# Connectors.net
KiCad netlist of a schematic drawn in Altium Designer
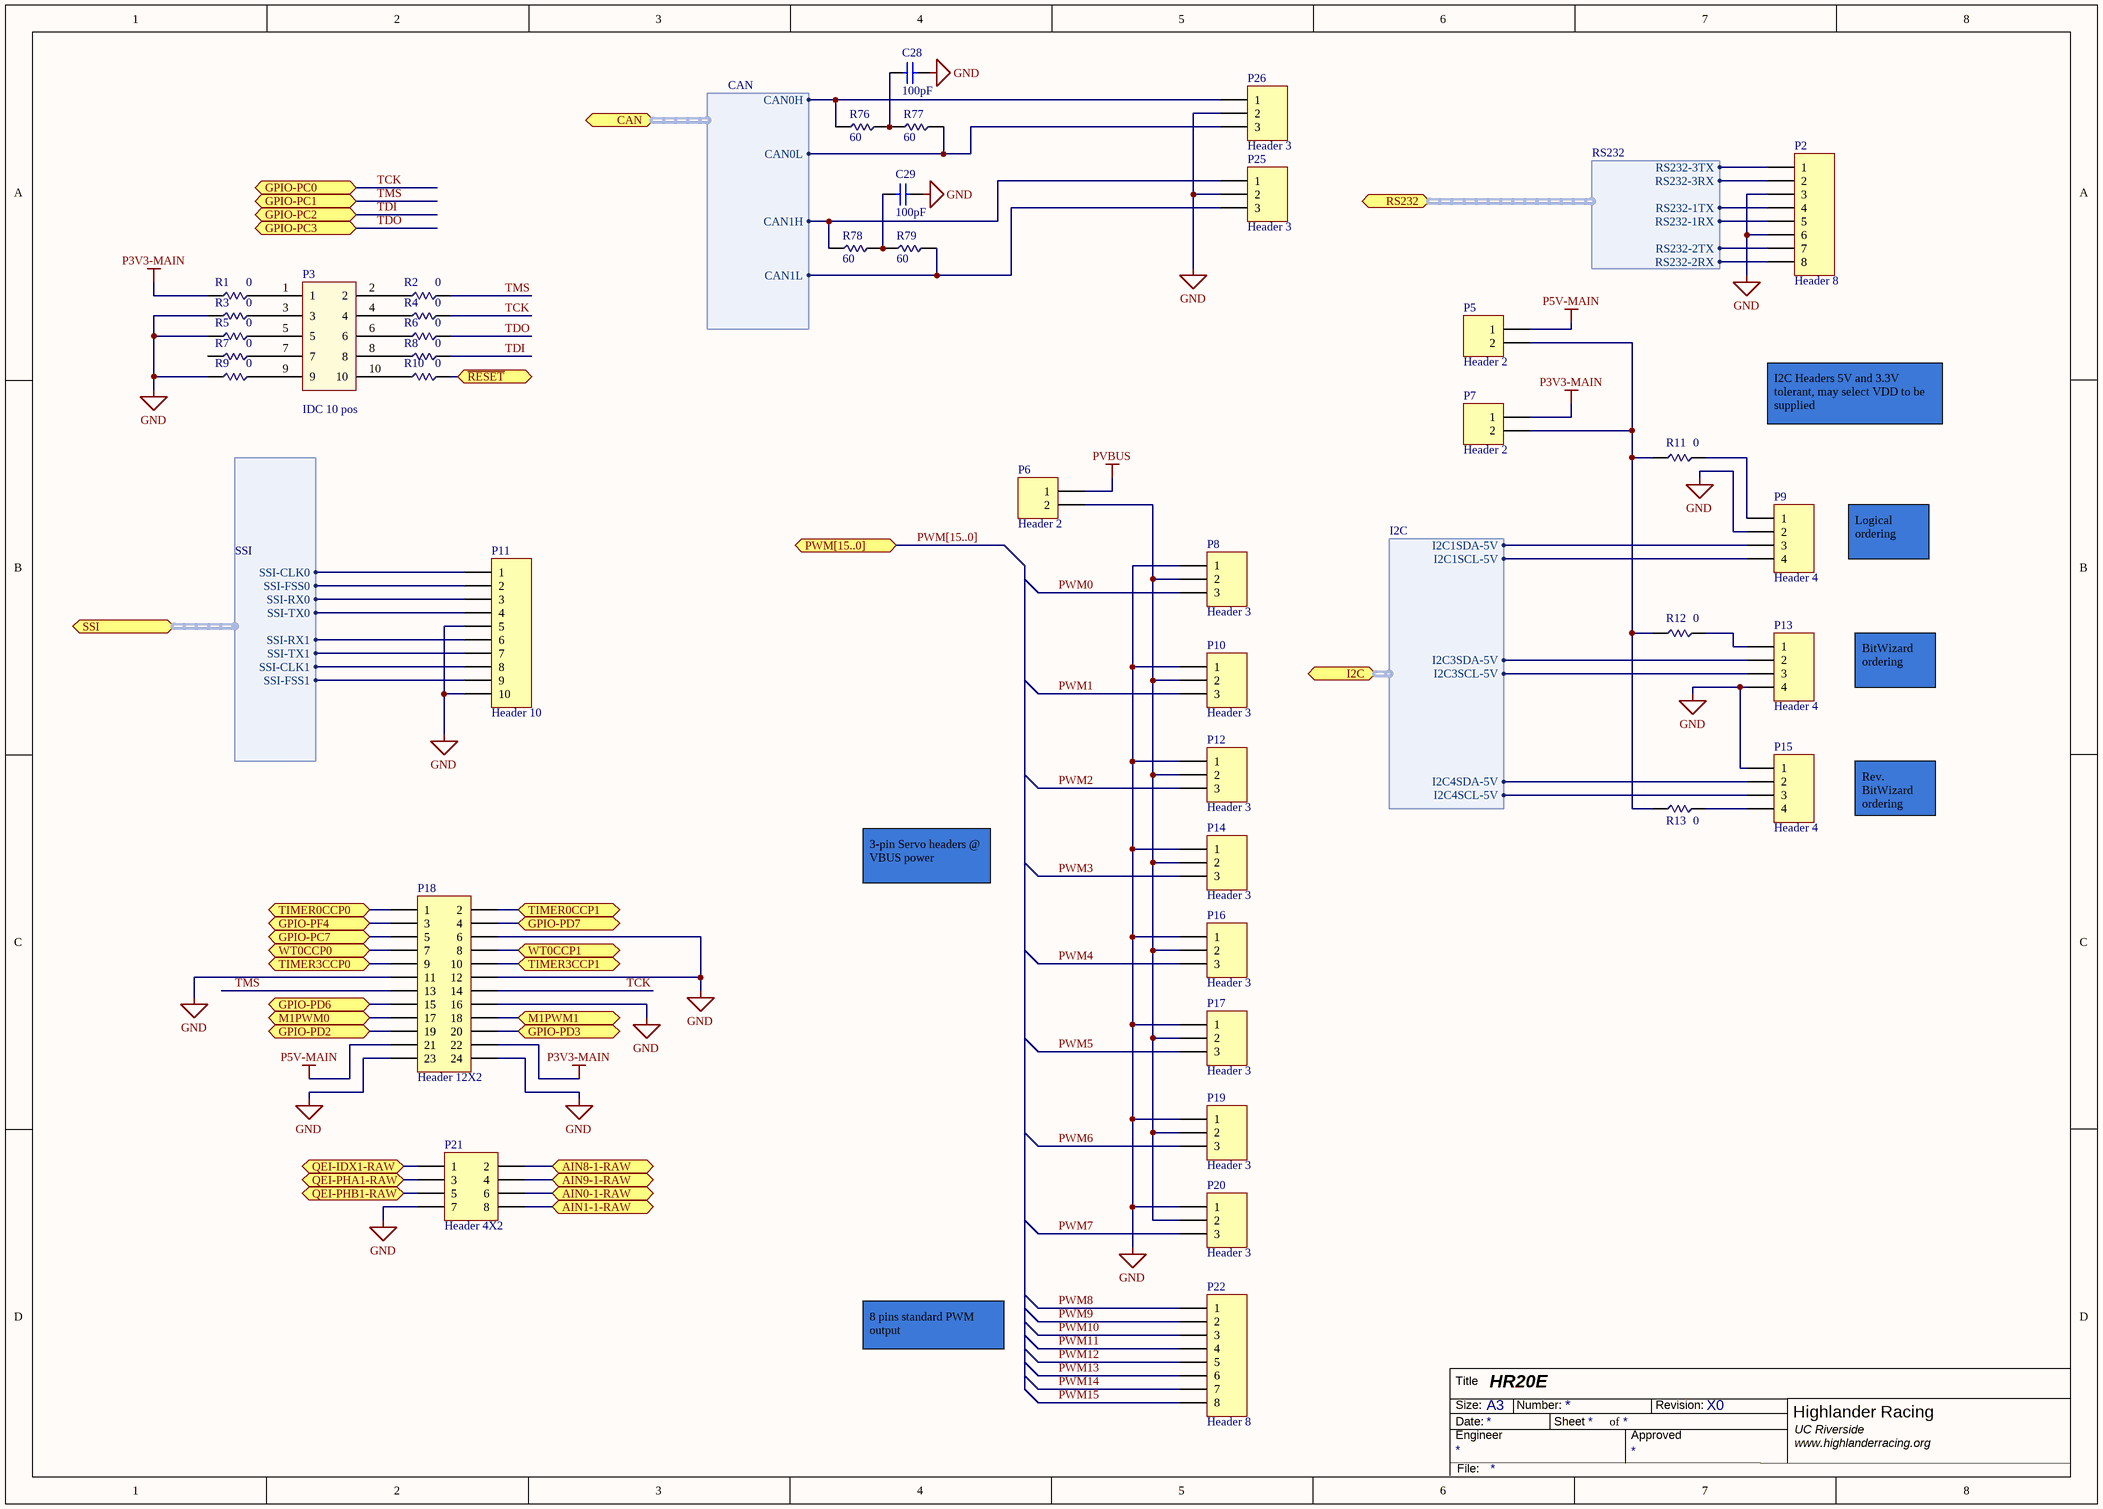
[diagram p0: Connectors.SchDoc]

(export (version "E")
  (design (tool "Eeschema 10.0.6"))
  (components
    (comp (ref "C28")
      (value "100pF")
      (footprint "FOOTPRINT-0805-GEN")
      (description "Capacitor")
      (fields (field (name "Comment") "Capacitor-Generic-0805") (field (name "PUBLISHER") "Altium Limited"))
      (libsource (lib "HR-Master-Integrated") (part "Capacitor-Generic-0805"))
    )
    (comp (ref "C29")
      (value "100pF")
      (footprint "FOOTPRINT-0805-GEN")
      (description "Capacitor")
      (fields (field (name "Comment") "Capacitor-Generic-0805") (field (name "PUBLISHER") "Altium Limited"))
      (libsource (lib "HR-Master-Integrated") (part "Capacitor-Generic-0805"))
    )
    (comp (ref "P2")
      (value "Header 8")
      (footprint "HDR1X8")
      (description "Header, 8-Pin")
      (fields (field (name "PUBLISHER") "Altium Limited"))
      (libsource (lib "AT-Misc-Connectors") (part "Header 8"))
    )
    (comp (ref "P3")
      (value "IDC 10 pos")
      (footprint "FOOTPRINT-GENERIC-10-HEADER-0MM5")
      (libsource (lib "HR-Master-Integrated") (part "Connector-Generic-Header-10-0mm5"))
    )
    (comp (ref "P5")
      (value "Header 2")
      (footprint "HDR1X2")
      (description "Header, 2-Pin")
      (fields (field (name "PUBLISHER") "Altium Limited"))
      (libsource (lib "AT-Misc-Connectors") (part "Header 2"))
    )
    (comp (ref "P6")
      (value "Header 2")
      (footprint "HDR1X2")
      (description "Header, 2-Pin")
      (fields (field (name "PUBLISHER") "Altium Limited"))
      (libsource (lib "AT-Misc-Connectors") (part "Header 2"))
    )
    (comp (ref "P7")
      (value "Header 2")
      (footprint "HDR1X2")
      (description "Header, 2-Pin")
      (fields (field (name "PUBLISHER") "Altium Limited"))
      (libsource (lib "AT-Misc-Connectors") (part "Header 2"))
    )
    (comp (ref "P8")
      (value "Header 3")
      (footprint "HDR1X3")
      (description "Header, 3-Pin")
      (fields (field (name "PUBLISHER") "Altium Limited"))
      (libsource (lib "AT-Misc-Connectors") (part "Header 3"))
    )
    (comp (ref "P9")
      (value "Header 4")
      (footprint "HDR1X4")
      (description "Header, 4-Pin")
      (fields (field (name "PUBLISHER") "Altium Limited"))
      (libsource (lib "AT-Misc-Connectors") (part "Header 4"))
    )
    (comp (ref "P10")
      (value "Header 3")
      (footprint "HDR1X3")
      (description "Header, 3-Pin")
      (fields (field (name "PUBLISHER") "Altium Limited"))
      (libsource (lib "AT-Misc-Connectors") (part "Header 3"))
    )
    (comp (ref "P11")
      (value "Header 10")
      (footprint "HDR1X10")
      (description "Header, 10-Pin")
      (fields (field (name "PUBLISHER") "Altium Limited"))
      (libsource (lib "AT-Misc-Connectors") (part "Header 10"))
    )
    (comp (ref "P12")
      (value "Header 3")
      (footprint "HDR1X3")
      (description "Header, 3-Pin")
      (fields (field (name "PUBLISHER") "Altium Limited"))
      (libsource (lib "AT-Misc-Connectors") (part "Header 3"))
    )
    (comp (ref "P13")
      (value "Header 4")
      (footprint "HDR1X4")
      (description "Header, 4-Pin")
      (fields (field (name "PUBLISHER") "Altium Limited"))
      (libsource (lib "AT-Misc-Connectors") (part "Header 4"))
    )
    (comp (ref "P14")
      (value "Header 3")
      (footprint "HDR1X3")
      (description "Header, 3-Pin")
      (fields (field (name "PUBLISHER") "Altium Limited"))
      (libsource (lib "AT-Misc-Connectors") (part "Header 3"))
    )
    (comp (ref "P15")
      (value "Header 4")
      (footprint "HDR1X4")
      (description "Header, 4-Pin")
      (fields (field (name "PUBLISHER") "Altium Limited"))
      (libsource (lib "AT-Misc-Connectors") (part "Header 4"))
    )
    (comp (ref "P16")
      (value "Header 3")
      (footprint "HDR1X3")
      (description "Header, 3-Pin")
      (fields (field (name "PUBLISHER") "Altium Limited"))
      (libsource (lib "AT-Misc-Connectors") (part "Header 3"))
    )
    (comp (ref "P17")
      (value "Header 3")
      (footprint "HDR1X3")
      (description "Header, 3-Pin")
      (fields (field (name "PUBLISHER") "Altium Limited"))
      (libsource (lib "AT-Misc-Connectors") (part "Header 3"))
    )
    (comp (ref "P18")
      (value "Header 12X2")
      (footprint "HDR2X12")
      (description "Header, 12-Pin, Dual row")
      (fields (field (name "PUBLISHER") "Altium Limited"))
      (libsource (lib "AT-Misc-Connectors") (part "Header 12X2"))
    )
    (comp (ref "P19")
      (value "Header 3")
      (footprint "HDR1X3")
      (description "Header, 3-Pin")
      (fields (field (name "PUBLISHER") "Altium Limited"))
      (libsource (lib "AT-Misc-Connectors") (part "Header 3"))
    )
    (comp (ref "P20")
      (value "Header 3")
      (footprint "HDR1X3")
      (description "Header, 3-Pin")
      (fields (field (name "PUBLISHER") "Altium Limited"))
      (libsource (lib "AT-Misc-Connectors") (part "Header 3"))
    )
    (comp (ref "P21")
      (value "Header 4X2")
      (footprint "HDR2X4")
      (description "Header, 4-Pin, Dual row")
      (fields (field (name "PUBLISHER") "Altium Limited"))
      (libsource (lib "AT-Misc-Connectors") (part "Header 4X2"))
    )
    (comp (ref "P22")
      (value "Header 8")
      (footprint "HDR1X8")
      (description "Header, 8-Pin")
      (fields (field (name "PUBLISHER") "Altium Limited"))
      (libsource (lib "AT-Misc-Connectors") (part "Header 8"))
    )
    (comp (ref "P25")
      (value "Header 3")
      (footprint "HDR1X3")
      (description "Header, 3-Pin")
      (fields (field (name "PUBLISHER") "Altium Limited"))
      (libsource (lib "AT-Misc-Connectors") (part "Header 3"))
    )
    (comp (ref "P26")
      (value "Header 3")
      (footprint "HDR1X3")
      (description "Header, 3-Pin")
      (fields (field (name "PUBLISHER") "Altium Limited"))
      (libsource (lib "AT-Misc-Connectors") (part "Header 3"))
    )
    (comp (ref "R1")
      (value "0")
      (footprint "FOOTPRINT-0805-GEN")
      (description "1/8 Watt Surface Mount Resistor")
      (fields (field (name "Comment") "SMC"))
      (libsource (lib "HR-Master-Integrated") (part "Resistor-Generic-0805-2012"))
    )
    (comp (ref "R2")
      (value "0")
      (footprint "FOOTPRINT-0805-GEN")
      (description "1/8 Watt Surface Mount Resistor")
      (fields (field (name "Comment") "SMC"))
      (libsource (lib "HR-Master-Integrated") (part "Resistor-Generic-0805-2012"))
    )
    (comp (ref "R3")
      (value "0")
      (footprint "FOOTPRINT-0805-GEN")
      (description "1/8 Watt Surface Mount Resistor")
      (fields (field (name "Comment") "SMC"))
      (libsource (lib "HR-Master-Integrated") (part "Resistor-Generic-0805-2012"))
    )
    (comp (ref "R4")
      (value "0")
      (footprint "FOOTPRINT-0805-GEN")
      (description "1/8 Watt Surface Mount Resistor")
      (fields (field (name "Comment") "SMC"))
      (libsource (lib "HR-Master-Integrated") (part "Resistor-Generic-0805-2012"))
    )
    (comp (ref "R5")
      (value "0")
      (footprint "FOOTPRINT-0805-GEN")
      (description "1/8 Watt Surface Mount Resistor")
      (fields (field (name "Comment") "SMC"))
      (libsource (lib "HR-Master-Integrated") (part "Resistor-Generic-0805-2012"))
    )
    (comp (ref "R6")
      (value "0")
      (footprint "FOOTPRINT-0805-GEN")
      (description "1/8 Watt Surface Mount Resistor")
      (fields (field (name "Comment") "SMC"))
      (libsource (lib "HR-Master-Integrated") (part "Resistor-Generic-0805-2012"))
    )
    (comp (ref "R7")
      (value "0")
      (footprint "FOOTPRINT-0805-GEN")
      (description "1/8 Watt Surface Mount Resistor")
      (fields (field (name "Comment") "SMC"))
      (libsource (lib "HR-Master-Integrated") (part "Resistor-Generic-0805-2012"))
    )
    (comp (ref "R8")
      (value "0")
      (footprint "FOOTPRINT-0805-GEN")
      (description "1/8 Watt Surface Mount Resistor")
      (fields (field (name "Comment") "SMC"))
      (libsource (lib "HR-Master-Integrated") (part "Resistor-Generic-0805-2012"))
    )
    (comp (ref "R9")
      (value "0")
      (footprint "FOOTPRINT-0805-GEN")
      (description "1/8 Watt Surface Mount Resistor")
      (fields (field (name "Comment") "SMC"))
      (libsource (lib "HR-Master-Integrated") (part "Resistor-Generic-0805-2012"))
    )
    (comp (ref "R10")
      (value "0")
      (footprint "FOOTPRINT-0805-GEN")
      (description "1/8 Watt Surface Mount Resistor")
      (fields (field (name "Comment") "SMC"))
      (libsource (lib "HR-Master-Integrated") (part "Resistor-Generic-0805-2012"))
    )
    (comp (ref "R11")
      (value "0")
      (footprint "FOOTPRINT-0805-GEN")
      (description "1/8 Watt Surface Mount Resistor")
      (fields (field (name "Comment") "SMC"))
      (libsource (lib "HR-Master-Integrated") (part "Resistor-Generic-0805-2012"))
    )
    (comp (ref "R12")
      (value "0")
      (footprint "FOOTPRINT-0805-GEN")
      (description "1/8 Watt Surface Mount Resistor")
      (fields (field (name "Comment") "SMC"))
      (libsource (lib "HR-Master-Integrated") (part "Resistor-Generic-0805-2012"))
    )
    (comp (ref "R13")
      (value "0")
      (footprint "FOOTPRINT-0805-GEN")
      (description "1/8 Watt Surface Mount Resistor")
      (fields (field (name "Comment") "SMC"))
      (libsource (lib "HR-Master-Integrated") (part "Resistor-Generic-0805-2012"))
    )
    (comp (ref "R76")
      (value "60")
      (footprint "FOOTPRINT-0805-GEN")
      (description "1/8 Watt Surface Mount Resistor")
      (fields (field (name "Comment") "SMC"))
      (libsource (lib "HR-Master-Integrated") (part "Resistor-Generic-0805-2012"))
    )
    (comp (ref "R77")
      (value "60")
      (footprint "FOOTPRINT-0805-GEN")
      (description "1/8 Watt Surface Mount Resistor")
      (fields (field (name "Comment") "SMC"))
      (libsource (lib "HR-Master-Integrated") (part "Resistor-Generic-0805-2012"))
    )
    (comp (ref "R78")
      (value "60")
      (footprint "FOOTPRINT-0805-GEN")
      (description "1/8 Watt Surface Mount Resistor")
      (fields (field (name "Comment") "SMC"))
      (libsource (lib "HR-Master-Integrated") (part "Resistor-Generic-0805-2012"))
    )
    (comp (ref "R79")
      (value "60")
      (footprint "FOOTPRINT-0805-GEN")
      (description "1/8 Watt Surface Mount Resistor")
      (fields (field (name "Comment") "SMC"))
      (libsource (lib "HR-Master-Integrated") (part "Resistor-Generic-0805-2012"))
    )
  )
  (nets
    (net (code "5") (name "/AIN0-1-RAW") (class "Default")
      (node (ref "P21") (pin "6") (pinfunction "6_6") (pintype "passive"))
    )
    (net (code "6") (name "/AIN1-1-RAW") (class "Default")
      (node (ref "P21") (pin "8") (pinfunction "8_8") (pintype "passive"))
    )
    (net (code "7") (name "/AIN8-1-RAW") (class "Default")
      (node (ref "P21") (pin "2") (pinfunction "2_2") (pintype "passive"))
    )
    (net (code "8") (name "/AIN9-1-RAW") (class "Default")
      (node (ref "P21") (pin "4") (pinfunction "4_4") (pintype "passive"))
    )
    (net (code "9") (name "/CAN0H") (class "Default")
      (node (ref "P26") (pin "1") (pinfunction "1_1") (pintype "passive"))
      (node (ref "R76") (pin "2") (pinfunction "2_2") (pintype "passive"))
    )
    (net (code "10") (name "/CAN0L") (class "Default")
      (node (ref "P26") (pin "3") (pinfunction "3_3") (pintype "passive"))
      (node (ref "R77") (pin "1") (pinfunction "1_1") (pintype "passive"))
    )
    (net (code "11") (name "/CAN1H") (class "Default")
      (node (ref "P25") (pin "1") (pinfunction "1_1") (pintype "passive"))
      (node (ref "R78") (pin "2") (pinfunction "2_2") (pintype "passive"))
    )
    (net (code "12") (name "/CAN1L") (class "Default")
      (node (ref "P25") (pin "3") (pinfunction "3_3") (pintype "passive"))
      (node (ref "R79") (pin "1") (pinfunction "1_1") (pintype "passive"))
    )
    (net (code "13") (name "/GPIO-PC7") (class "Default")
      (node (ref "P18") (pin "5") (pinfunction "5_5") (pintype "passive"))
    )
    (net (code "14") (name "/GPIO-PD2") (class "Default")
      (node (ref "P18") (pin "19") (pinfunction "19_19") (pintype "passive"))
    )
    (net (code "15") (name "/GPIO-PD3") (class "Default")
      (node (ref "P18") (pin "20") (pinfunction "20_20") (pintype "passive"))
    )
    (net (code "16") (name "/GPIO-PD6") (class "Default")
      (node (ref "P18") (pin "15") (pinfunction "15_15") (pintype "passive"))
    )
    (net (code "17") (name "/GPIO-PD7") (class "Default")
      (node (ref "P18") (pin "4") (pinfunction "4_4") (pintype "passive"))
    )
    (net (code "18") (name "/GPIO-PF4") (class "Default")
      (node (ref "P18") (pin "3") (pinfunction "3_3") (pintype "passive"))
    )
    (net (code "19") (name "/I2C1SCL-5V") (class "Default")
      (node (ref "P9") (pin "4") (pinfunction "4_4") (pintype "passive"))
    )
    (net (code "20") (name "/I2C1SDA-5V") (class "Default")
      (node (ref "P9") (pin "3") (pinfunction "3_3") (pintype "passive"))
    )
    (net (code "21") (name "/I2C3SCL-5V") (class "Default")
      (node (ref "P13") (pin "3") (pinfunction "3_3") (pintype "passive"))
    )
    (net (code "22") (name "/I2C3SDA-5V") (class "Default")
      (node (ref "P13") (pin "2") (pinfunction "2_2") (pintype "passive"))
    )
    (net (code "23") (name "/I2C4SCL-5V") (class "Default")
      (node (ref "P15") (pin "3") (pinfunction "3_3") (pintype "passive"))
    )
    (net (code "24") (name "/I2C4SDA-5V") (class "Default")
      (node (ref "P15") (pin "2") (pinfunction "2_2") (pintype "passive"))
    )
    (net (code "25") (name "/M1PWM0") (class "Default")
      (node (ref "P18") (pin "17") (pinfunction "17_17") (pintype "passive"))
    )
    (net (code "26") (name "/M1PWM1") (class "Default")
      (node (ref "P18") (pin "18") (pinfunction "18_18") (pintype "passive"))
    )
    (net (code "27") (name "/PWM0") (class "Default")
      (node (ref "P8") (pin "3") (pinfunction "3_3") (pintype "passive"))
    )
    (net (code "28") (name "/PWM1") (class "Default")
      (node (ref "P10") (pin "3") (pinfunction "3_3") (pintype "passive"))
    )
    (net (code "29") (name "/PWM2") (class "Default")
      (node (ref "P12") (pin "3") (pinfunction "3_3") (pintype "passive"))
    )
    (net (code "30") (name "/PWM3") (class "Default")
      (node (ref "P14") (pin "3") (pinfunction "3_3") (pintype "passive"))
    )
    (net (code "31") (name "/PWM4") (class "Default")
      (node (ref "P16") (pin "3") (pinfunction "3_3") (pintype "passive"))
    )
    (net (code "32") (name "/PWM5") (class "Default")
      (node (ref "P17") (pin "3") (pinfunction "3_3") (pintype "passive"))
    )
    (net (code "33") (name "/PWM6") (class "Default")
      (node (ref "P19") (pin "3") (pinfunction "3_3") (pintype "passive"))
    )
    (net (code "34") (name "/PWM7") (class "Default")
      (node (ref "P20") (pin "3") (pinfunction "3_3") (pintype "passive"))
    )
    (net (code "35") (name "/PWM8") (class "Default")
      (node (ref "P22") (pin "1") (pinfunction "1_1") (pintype "passive"))
    )
    (net (code "36") (name "/PWM9") (class "Default")
      (node (ref "P22") (pin "2") (pinfunction "2_2") (pintype "passive"))
    )
    (net (code "37") (name "/PWM10") (class "Default")
      (node (ref "P22") (pin "3") (pinfunction "3_3") (pintype "passive"))
    )
    (net (code "38") (name "/PWM11") (class "Default")
      (node (ref "P22") (pin "4") (pinfunction "4_4") (pintype "passive"))
    )
    (net (code "39") (name "/PWM12") (class "Default")
      (node (ref "P22") (pin "5") (pinfunction "5_5") (pintype "passive"))
    )
    (net (code "40") (name "/PWM13") (class "Default")
      (node (ref "P22") (pin "6") (pinfunction "6_6") (pintype "passive"))
    )
    (net (code "41") (name "/PWM14") (class "Default")
      (node (ref "P22") (pin "7") (pinfunction "7_7") (pintype "passive"))
    )
    (net (code "42") (name "/PWM15") (class "Default")
      (node (ref "P22") (pin "8") (pinfunction "8_8") (pintype "passive"))
    )
    (net (code "44") (name "/QEI-IDX1-RAW") (class "Default")
      (node (ref "P21") (pin "1") (pinfunction "1_1") (pintype "passive"))
    )
    (net (code "45") (name "/QEI-PHA1-RAW") (class "Default")
      (node (ref "P21") (pin "3") (pinfunction "3_3") (pintype "passive"))
    )
    (net (code "46") (name "/QEI-PHB1-RAW") (class "Default")
      (node (ref "P21") (pin "5") (pinfunction "5_5") (pintype "passive"))
    )
    (net (code "47") (name "/RESET") (class "Default")
      (node (ref "R10") (pin "2") (pinfunction "2_2") (pintype "passive"))
    )
    (net (code "48") (name "/RS232-1RX") (class "Default")
      (node (ref "P2") (pin "5") (pinfunction "5_5") (pintype "passive"))
    )
    (net (code "49") (name "/RS232-1TX") (class "Default")
      (node (ref "P2") (pin "4") (pinfunction "4_4") (pintype "passive"))
    )
    (net (code "50") (name "/RS232-2RX") (class "Default")
      (node (ref "P2") (pin "8") (pinfunction "8_8") (pintype "passive"))
    )
    (net (code "51") (name "/RS232-2TX") (class "Default")
      (node (ref "P2") (pin "7") (pinfunction "7_7") (pintype "passive"))
    )
    (net (code "52") (name "/RS232-3RX") (class "Default")
      (node (ref "P2") (pin "2") (pinfunction "2_2") (pintype "passive"))
    )
    (net (code "53") (name "/RS232-3TX") (class "Default")
      (node (ref "P2") (pin "1") (pinfunction "1_1") (pintype "passive"))
    )
    (net (code "54") (name "/SSI-CLK0") (class "Default")
      (node (ref "P11") (pin "1") (pinfunction "1_1") (pintype "passive"))
    )
    (net (code "55") (name "/SSI-CLK1") (class "Default")
      (node (ref "P11") (pin "8") (pinfunction "8_8") (pintype "passive"))
    )
    (net (code "56") (name "/SSI-FSS0") (class "Default")
      (node (ref "P11") (pin "2") (pinfunction "2_2") (pintype "passive"))
    )
    (net (code "57") (name "/SSI-FSS1") (class "Default")
      (node (ref "P11") (pin "9") (pinfunction "9_9") (pintype "passive"))
    )
    (net (code "58") (name "/SSI-RX0") (class "Default")
      (node (ref "P11") (pin "3") (pinfunction "3_3") (pintype "passive"))
    )
    (net (code "59") (name "/SSI-RX1") (class "Default")
      (node (ref "P11") (pin "6") (pinfunction "6_6") (pintype "passive"))
    )
    (net (code "60") (name "/SSI-TX0") (class "Default")
      (node (ref "P11") (pin "4") (pinfunction "4_4") (pintype "passive"))
    )
    (net (code "61") (name "/SSI-TX1") (class "Default")
      (node (ref "P11") (pin "7") (pinfunction "7_7") (pintype "passive"))
    )
    (net (code "62") (name "/TCK") (class "Default")
      (node (ref "P18") (pin "14") (pinfunction "14_14") (pintype "passive"))
      (node (ref "R4") (pin "2") (pinfunction "2_2") (pintype "passive"))
    )
    (net (code "63") (name "/TDI") (class "Default")
      (node (ref "R8") (pin "2") (pinfunction "2_2") (pintype "passive"))
    )
    (net (code "64") (name "/TDO") (class "Default")
      (node (ref "R6") (pin "2") (pinfunction "2_2") (pintype "passive"))
    )
    (net (code "65") (name "/TIMER0CCP0") (class "Default")
      (node (ref "P18") (pin "1") (pinfunction "1_1") (pintype "passive"))
    )
    (net (code "66") (name "/TIMER0CCP1") (class "Default")
      (node (ref "P18") (pin "2") (pinfunction "2_2") (pintype "passive"))
    )
    (net (code "67") (name "/TIMER3CCP0") (class "Default")
      (node (ref "P18") (pin "9") (pinfunction "9_9") (pintype "passive"))
    )
    (net (code "68") (name "/TIMER3CCP1") (class "Default")
      (node (ref "P18") (pin "10") (pinfunction "10_10") (pintype "passive"))
    )
    (net (code "69") (name "/TMS") (class "Default")
      (node (ref "P18") (pin "13") (pinfunction "13_13") (pintype "passive"))
      (node (ref "R2") (pin "2") (pinfunction "2_2") (pintype "passive"))
    )
    (net (code "70") (name "/WT0CCP0") (class "Default")
      (node (ref "P18") (pin "7") (pinfunction "7_7") (pintype "passive"))
    )
    (net (code "71") (name "/WT0CCP1") (class "Default")
      (node (ref "P18") (pin "8") (pinfunction "8_8") (pintype "passive"))
    )
    (net (code "76") (name "GND") (class "Default")
      (node (ref "C28") (pin "2") (pinfunction "2_2") (pintype "passive"))
      (node (ref "C29") (pin "2") (pinfunction "2_2") (pintype "passive"))
      (node (ref "P10") (pin "1") (pinfunction "1_1") (pintype "passive"))
      (node (ref "P11") (pin "10") (pinfunction "10_10") (pintype "passive"))
      (node (ref "P11") (pin "5") (pinfunction "5_5") (pintype "passive"))
      (node (ref "P12") (pin "1") (pinfunction "1_1") (pintype "passive"))
      (node (ref "P13") (pin "4") (pinfunction "4_4") (pintype "passive"))
      (node (ref "P14") (pin "1") (pinfunction "1_1") (pintype "passive"))
      (node (ref "P15") (pin "1") (pinfunction "1_1") (pintype "passive"))
      (node (ref "P16") (pin "1") (pinfunction "1_1") (pintype "passive"))
      (node (ref "P17") (pin "1") (pinfunction "1_1") (pintype "passive"))
      (node (ref "P18") (pin "11") (pinfunction "11_11") (pintype "passive"))
      (node (ref "P18") (pin "12") (pinfunction "12_12") (pintype "passive"))
      (node (ref "P18") (pin "16") (pinfunction "16_16") (pintype "passive"))
      (node (ref "P18") (pin "23") (pinfunction "23_23") (pintype "passive"))
      (node (ref "P18") (pin "24") (pinfunction "24_24") (pintype "passive"))
      (node (ref "P18") (pin "6") (pinfunction "6_6") (pintype "passive"))
      (node (ref "P19") (pin "1") (pinfunction "1_1") (pintype "passive"))
      (node (ref "P2") (pin "3") (pinfunction "3_3") (pintype "passive"))
      (node (ref "P2") (pin "6") (pinfunction "6_6") (pintype "passive"))
      (node (ref "P20") (pin "1") (pinfunction "1_1") (pintype "passive"))
      (node (ref "P21") (pin "7") (pinfunction "7_7") (pintype "passive"))
      (node (ref "P25") (pin "2") (pinfunction "2_2") (pintype "passive"))
      (node (ref "P26") (pin "2") (pinfunction "2_2") (pintype "passive"))
      (node (ref "P8") (pin "1") (pinfunction "1_1") (pintype "passive"))
      (node (ref "P9") (pin "2") (pinfunction "2_2") (pintype "passive"))
      (node (ref "R3") (pin "1") (pinfunction "1_1") (pintype "passive"))
      (node (ref "R5") (pin "1") (pinfunction "1_1") (pintype "passive"))
      (node (ref "R9") (pin "1") (pinfunction "1_1") (pintype "passive"))
    )
    (net (code "77") (name "Net-(C28-Pad1)") (class "Default")
      (node (ref "C28") (pin "1") (pinfunction "1_1") (pintype "passive"))
      (node (ref "R76") (pin "1") (pinfunction "1_1") (pintype "passive"))
      (node (ref "R77") (pin "2") (pinfunction "2_2") (pintype "passive"))
    )
    (net (code "78") (name "Net-(C29-Pad1)") (class "Default")
      (node (ref "C29") (pin "1") (pinfunction "1_1") (pintype "passive"))
      (node (ref "R78") (pin "1") (pinfunction "1_1") (pintype "passive"))
      (node (ref "R79") (pin "2") (pinfunction "2_2") (pintype "passive"))
    )
    (net (code "79") (name "Net-(P3-Pad1)") (class "Default")
      (node (ref "P3") (pin "1") (pinfunction "1_1") (pintype "passive"))
      (node (ref "R1") (pin "2") (pinfunction "2_2") (pintype "passive"))
    )
    (net (code "80") (name "Net-(P3-Pad2)") (class "Default")
      (node (ref "P3") (pin "2") (pinfunction "2_2") (pintype "passive"))
      (node (ref "R2") (pin "1") (pinfunction "1_1") (pintype "passive"))
    )
    (net (code "81") (name "Net-(P3-Pad3)") (class "Default")
      (node (ref "P3") (pin "3") (pinfunction "3_3") (pintype "passive"))
      (node (ref "R3") (pin "2") (pinfunction "2_2") (pintype "passive"))
    )
    (net (code "82") (name "Net-(P3-Pad4)") (class "Default")
      (node (ref "P3") (pin "4") (pinfunction "4_4") (pintype "passive"))
      (node (ref "R4") (pin "1") (pinfunction "1_1") (pintype "passive"))
    )
    (net (code "83") (name "Net-(P3-Pad5)") (class "Default")
      (node (ref "P3") (pin "5") (pinfunction "5_5") (pintype "passive"))
      (node (ref "R5") (pin "2") (pinfunction "2_2") (pintype "passive"))
    )
    (net (code "84") (name "Net-(P3-Pad6)") (class "Default")
      (node (ref "P3") (pin "6") (pinfunction "6_6") (pintype "passive"))
      (node (ref "R6") (pin "1") (pinfunction "1_1") (pintype "passive"))
    )
    (net (code "85") (name "Net-(P3-Pad7)") (class "Default")
      (node (ref "P3") (pin "7") (pinfunction "7_7") (pintype "passive"))
      (node (ref "R7") (pin "2") (pinfunction "2_2") (pintype "passive"))
    )
    (net (code "86") (name "Net-(P3-Pad8)") (class "Default")
      (node (ref "P3") (pin "8") (pinfunction "8_8") (pintype "passive"))
      (node (ref "R8") (pin "1") (pinfunction "1_1") (pintype "passive"))
    )
    (net (code "87") (name "Net-(P3-Pad9)") (class "Default")
      (node (ref "P3") (pin "9") (pinfunction "9_9") (pintype "passive"))
      (node (ref "R9") (pin "2") (pinfunction "2_2") (pintype "passive"))
    )
    (net (code "88") (name "Net-(P3-Pad10)") (class "Default")
      (node (ref "P3") (pin "10") (pinfunction "10_10") (pintype "passive"))
      (node (ref "R10") (pin "1") (pinfunction "1_1") (pintype "passive"))
    )
    (net (code "89") (name "Net-(P5-Pad2)") (class "Default")
      (node (ref "P5") (pin "2") (pinfunction "2_2") (pintype "passive"))
      (node (ref "P7") (pin "2") (pinfunction "2_2") (pintype "passive"))
      (node (ref "R11") (pin "1") (pinfunction "1_1") (pintype "passive"))
      (node (ref "R12") (pin "1") (pinfunction "1_1") (pintype "passive"))
      (node (ref "R13") (pin "1") (pinfunction "1_1") (pintype "passive"))
    )
    (net (code "90") (name "Net-(P9-Pad1)") (class "Default")
      (node (ref "P9") (pin "1") (pinfunction "1_1") (pintype "passive"))
      (node (ref "R11") (pin "2") (pinfunction "2_2") (pintype "passive"))
    )
    (net (code "91") (name "Net-(P10-Pad2)") (class "Default")
      (node (ref "P10") (pin "2") (pinfunction "2_2") (pintype "passive"))
      (node (ref "P12") (pin "2") (pinfunction "2_2") (pintype "passive"))
      (node (ref "P14") (pin "2") (pinfunction "2_2") (pintype "passive"))
      (node (ref "P16") (pin "2") (pinfunction "2_2") (pintype "passive"))
      (node (ref "P17") (pin "2") (pinfunction "2_2") (pintype "passive"))
      (node (ref "P19") (pin "2") (pinfunction "2_2") (pintype "passive"))
      (node (ref "P20") (pin "2") (pinfunction "2_2") (pintype "passive"))
      (node (ref "P6") (pin "2") (pinfunction "2_2") (pintype "passive"))
      (node (ref "P8") (pin "2") (pinfunction "2_2") (pintype "passive"))
    )
    (net (code "92") (name "Net-(P13-Pad1)") (class "Default")
      (node (ref "P13") (pin "1") (pinfunction "1_1") (pintype "passive"))
      (node (ref "R12") (pin "2") (pinfunction "2_2") (pintype "passive"))
    )
    (net (code "93") (name "Net-(P15-Pad4)") (class "Default")
      (node (ref "P15") (pin "4") (pinfunction "4_4") (pintype "passive"))
      (node (ref "R13") (pin "2") (pinfunction "2_2") (pintype "passive"))
    )
    (net (code "94") (name "P3V3-MAIN") (class "Default")
      (node (ref "P18") (pin "22") (pinfunction "22_22") (pintype "passive"))
      (node (ref "P7") (pin "1") (pinfunction "1_1") (pintype "passive"))
      (node (ref "R1") (pin "1") (pinfunction "1_1") (pintype "passive"))
    )
    (net (code "95") (name "P5V-MAIN") (class "Default")
      (node (ref "P18") (pin "21") (pinfunction "21_21") (pintype "passive"))
      (node (ref "P5") (pin "1") (pinfunction "1_1") (pintype "passive"))
    )
    (net (code "96") (name "PVBUS") (class "Default")
      (node (ref "P6") (pin "1") (pinfunction "1_1") (pintype "passive"))
    )
    (net (code "97") (name "unconnected-(R7-Pad1)") (class "Default")
      (node (ref "R7") (pin "1") (pinfunction "1_1") (pintype "passive"))
    )
  )
)
